# MainBoard_V03.net
KiCad netlist of a schematic drawn in Altium Designer
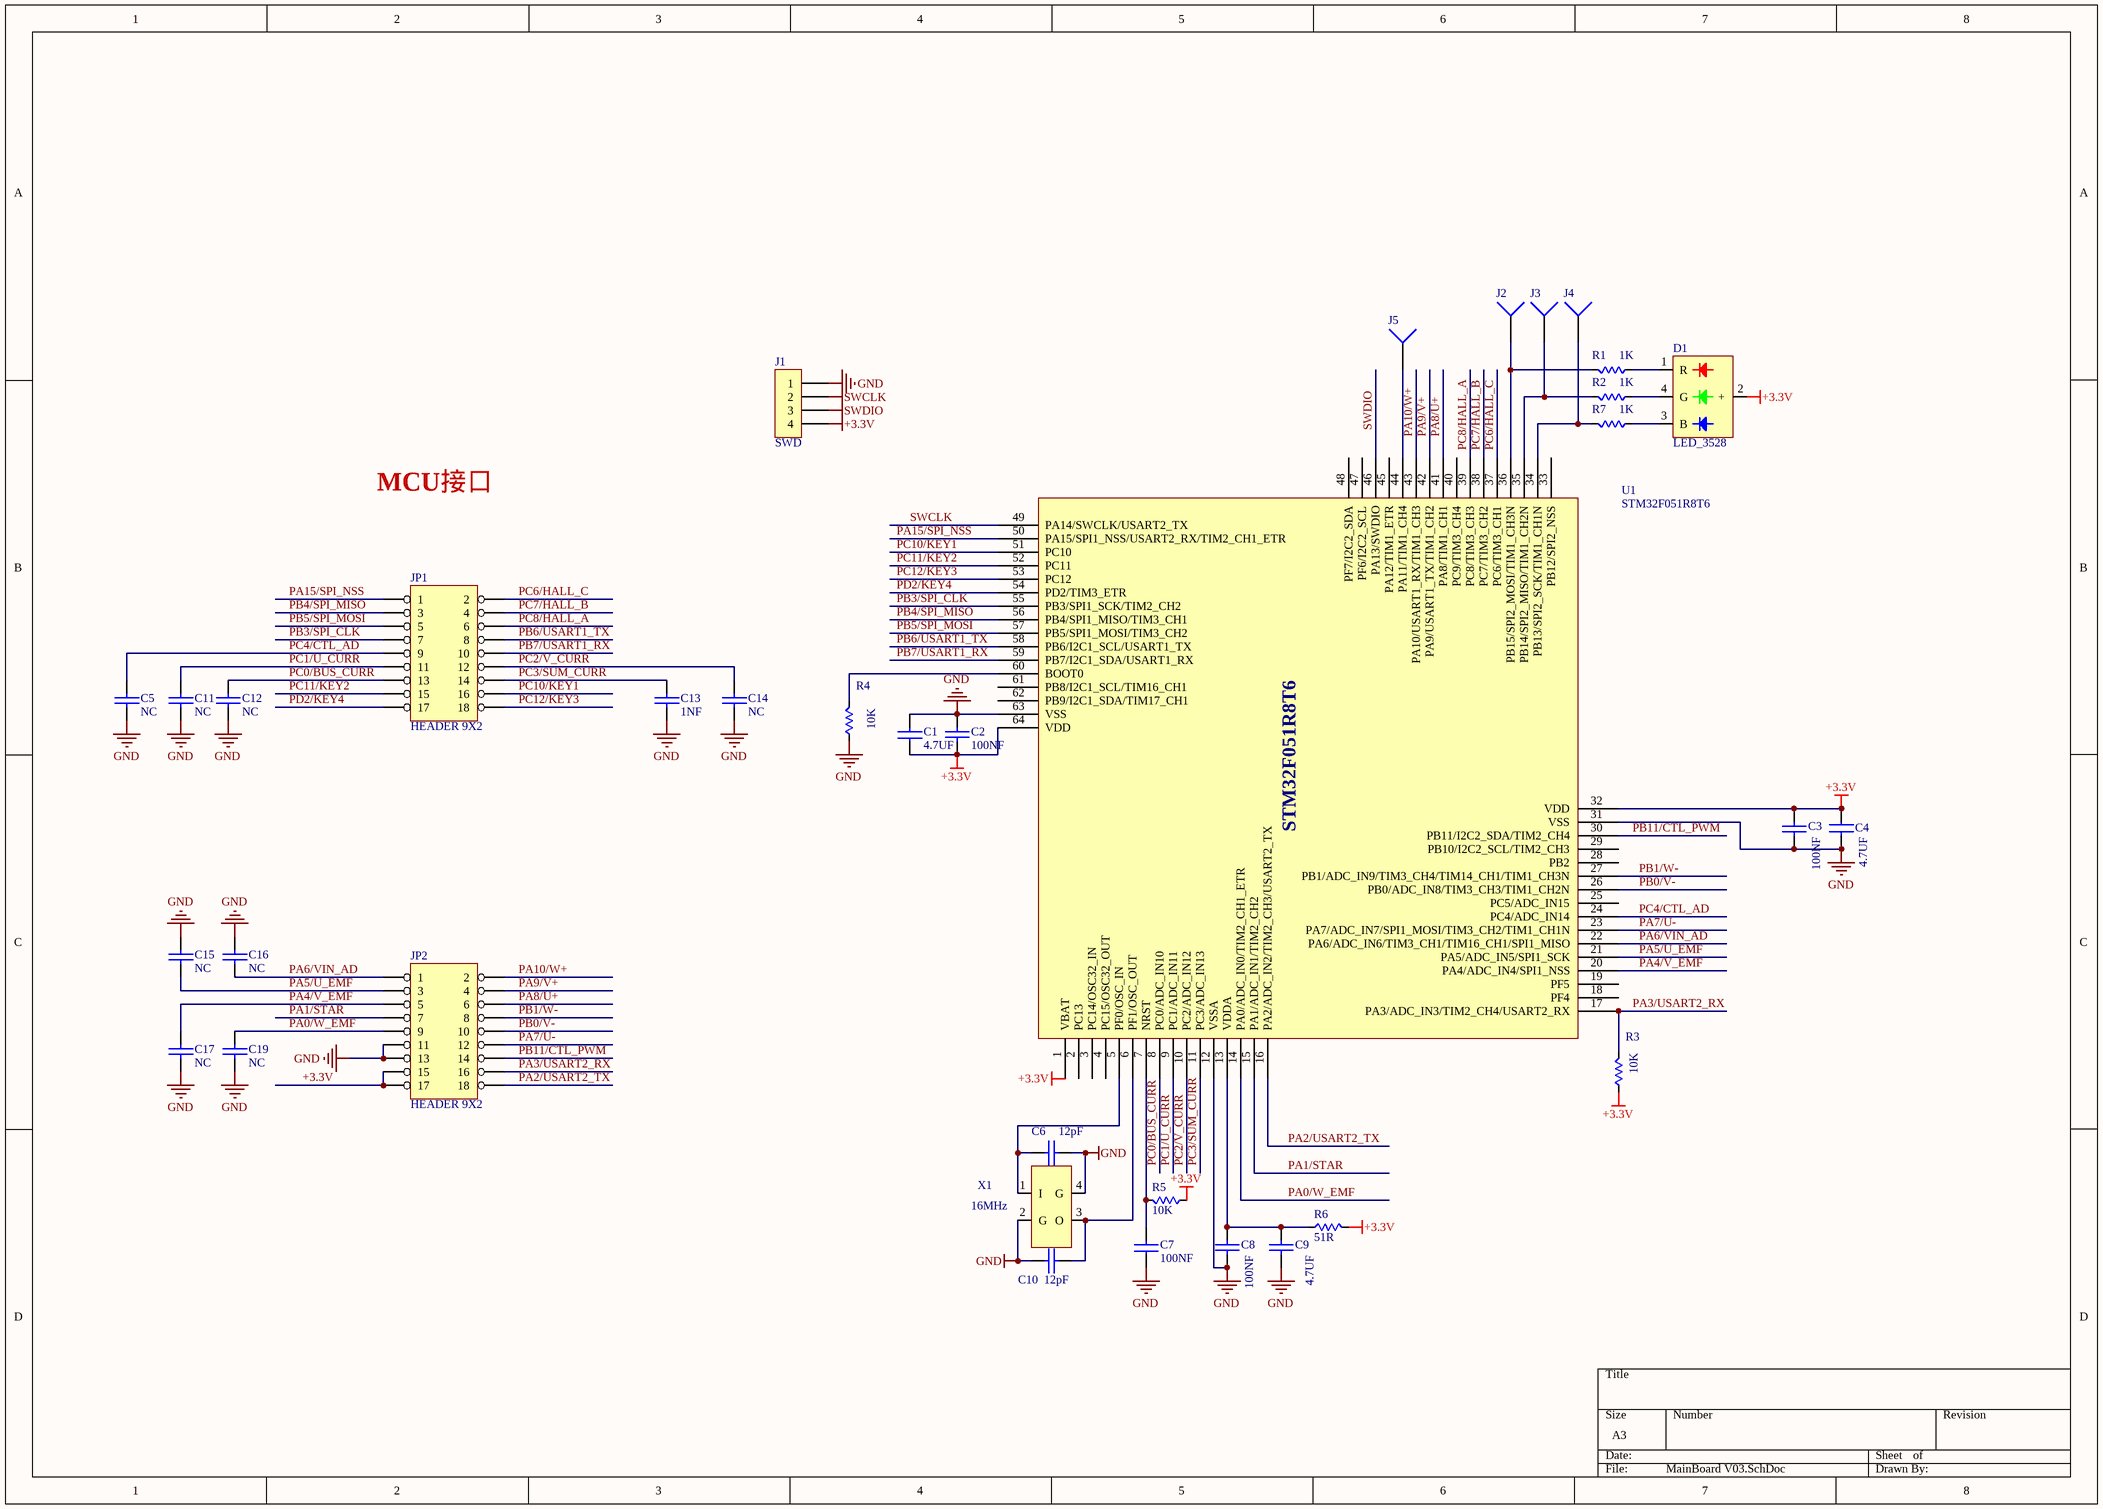
[diagram p0: MainBoard V03.SchDoc]

(export (version "E")
  (design (tool "Eeschema 10.0.6"))
  (components
    (comp (ref "C1") (value "4.7UF") (footprint "0805C") (libsource (lib "*") (part "CAP NP")))
    (comp (ref "C2")
      (value "100NF")
      (footprint "0603C")
      (description "Y02-02238")
      (libsource (lib "*") (part "CAP"))
    )
    (comp (ref "C3")
      (value "100NF")
      (footprint "0603C")
      (description "Y02-02238")
      (libsource (lib "*") (part "CAP"))
    )
    (comp (ref "C4") (value "4.7UF") (footprint "0805C") (libsource (lib "*") (part "CAP NP")))
    (comp (ref "C5")
      (value "NC")
      (footprint "0603C")
      (description "Y02-02238")
      (libsource (lib "*") (part "CAP"))
    )
    (comp (ref "C6")
      (value "12pF")
      (footprint "0603C")
      (description "Capacitor")
      (libsource (lib "*") (part "CAP"))
    )
    (comp (ref "C7")
      (value "100NF")
      (footprint "0603C")
      (description "Y02-02238")
      (libsource (lib "*") (part "CAP NP"))
    )
    (comp (ref "C8")
      (value "100NF")
      (footprint "0603C")
      (description "Y02-02238")
      (libsource (lib "*") (part "CAP"))
    )
    (comp (ref "C9")
      (value "4.7UF")
      (footprint "0805C")
      (description "Y02-02238")
      (libsource (lib "*") (part "CAP"))
    )
    (comp (ref "C10")
      (value "12pF")
      (footprint "0603C")
      (description "Capacitor")
      (libsource (lib "*") (part "CAP"))
    )
    (comp (ref "C11")
      (value "NC")
      (footprint "0603C")
      (description "Y02-02238")
      (libsource (lib "*") (part "CAP"))
    )
    (comp (ref "C12")
      (value "NC")
      (footprint "0603C")
      (description "Y02-02238")
      (libsource (lib "*") (part "CAP"))
    )
    (comp (ref "C13")
      (value "1NF")
      (footprint "0603C")
      (description "Y02-02238")
      (libsource (lib "*") (part "CAP"))
    )
    (comp (ref "C14")
      (value "NC")
      (footprint "0603C")
      (description "Y02-02238")
      (libsource (lib "*") (part "CAP"))
    )
    (comp (ref "C15")
      (value "NC")
      (footprint "0603C")
      (description "Y02-02238")
      (libsource (lib "*") (part "CAP"))
    )
    (comp (ref "C16")
      (value "NC")
      (footprint "0603C")
      (description "Y02-02238")
      (libsource (lib "*") (part "CAP"))
    )
    (comp (ref "C17")
      (value "NC")
      (footprint "0603C")
      (description "Y02-02238")
      (libsource (lib "*") (part "CAP"))
    )
    (comp (ref "C19")
      (value "NC")
      (footprint "0603C")
      (description "Y02-02238")
      (libsource (lib "*") (part "CAP"))
    )
    (comp (ref "D1") (value "LED_3528") (footprint "LED3528") (libsource (lib "COFLY-SCH") (part "LED_3528")))
    (comp (ref "J1")
      (value "SWD")
      (footprint "SIP4")
      (description "Connector")
      (libsource (lib "*") (part "CON4"))
    )
    (comp (ref "J2")
      (value "~")
      (footprint "TPJ1.3A")
      (description "Plug")
      (fields (field (name "PUBLISHER") "Altium Limited"))
      (libsource (lib "Miscellaneous Connectors") (part "Socket"))
    )
    (comp (ref "J3")
      (value "~")
      (footprint "TPJ1.3A")
      (description "Plug")
      (fields (field (name "PUBLISHER") "Altium Limited"))
      (libsource (lib "Miscellaneous Connectors") (part "Socket"))
    )
    (comp (ref "J4")
      (value "~")
      (footprint "TPJ1.3A")
      (description "Plug")
      (fields (field (name "PUBLISHER") "Altium Limited"))
      (libsource (lib "Miscellaneous Connectors") (part "Socket"))
    )
    (comp (ref "J5")
      (value "~")
      (footprint "PLUG")
      (description "Plug")
      (fields (field (name "PUBLISHER") "Altium Limited"))
      (libsource (lib "Miscellaneous Connectors") (part "Socket"))
    )
    (comp (ref "JP1")
      (value "HEADER 9X2")
      (footprint "SMT2.54-2X9-M-MIRROR")
      (libsource (lib "COFLY-SCH") (part "HEADER 9X2"))
    )
    (comp (ref "JP2")
      (value "HEADER 9X2")
      (footprint "SMT2.54-2X9-M-MIRROR")
      (libsource (lib "COFLY-SCH") (part "HEADER 9X2"))
    )
    (comp (ref "R1")
      (value "1K")
      (footprint "0603R")
      (description "Y02-00493")
      (libsource (lib "YUNEEC-SCH") (part "RES"))
    )
    (comp (ref "R2")
      (value "1K")
      (footprint "0603R")
      (description "Y02-00493")
      (libsource (lib "YUNEEC-SCH") (part "RES"))
    )
    (comp (ref "R3") (value "10K") (footprint "0603R") (libsource (lib "*") (part "RES")))
    (comp (ref "R4")
      (value "10K")
      (footprint "0603R")
      (description "Y02-01715")
      (libsource (lib "*") (part "RES"))
    )
    (comp (ref "R5")
      (value "10K")
      (footprint "0603R")
      (description "Y02-01715")
      (libsource (lib "*") (part "RES"))
    )
    (comp (ref "R6")
      (value "51R")
      (footprint "0603R")
      (description "Y02-01715")
      (libsource (lib "*") (part "RES"))
    )
    (comp (ref "R7")
      (value "1K")
      (footprint "0603R")
      (description "Y02-00493")
      (libsource (lib "YUNEEC-SCH") (part "RES"))
    )
    (comp (ref "U1")
      (value "STM32F051R8T6")
      (footprint "LQFP-64")
      (libsource (lib "COFLY-SCH") (part "STM32F051R8T6"))
    )
    (comp (ref "X1") (value "16MHz") (footprint "Y3225") (libsource (lib "*") (part "CON4A_1")))
  )
  (nets
    (net (code "1") (name "+3.3V") (class "Default")
      (node (ref "C1") (pin "1") (pinfunction "1_1") (pintype "passive"))
      (node (ref "C2") (pin "1") (pinfunction "1_1") (pintype "passive"))
      (node (ref "C3") (pin "1") (pinfunction "1_1") (pintype "passive"))
      (node (ref "C4") (pin "1") (pinfunction "1_1") (pintype "passive"))
      (node (ref "D1") (pin "2") (pinfunction "+_2") (pintype "passive"))
      (node (ref "J1") (pin "4") (pinfunction "4_4") (pintype "passive"))
      (node (ref "JP2") (pin "15") (pinfunction "15_15") (pintype "passive"))
      (node (ref "JP2") (pin "17") (pinfunction "17_17") (pintype "passive"))
      (node (ref "R3") (pin "2") (pinfunction "2_2") (pintype "passive"))
      (node (ref "R5") (pin "2") (pinfunction "2_2") (pintype "passive"))
      (node (ref "R6") (pin "1") (pinfunction "1_1") (pintype "passive"))
      (node (ref "U1") (pin "1") (pinfunction "VBAT_1") (pintype "passive"))
      (node (ref "U1") (pin "32") (pinfunction "VDD_32") (pintype "passive"))
      (node (ref "U1") (pin "64") (pinfunction "VDD_64") (pintype "passive"))
    )
    (net (code "2") (name "/PA0{slash}W_EMF") (class "Default")
      (node (ref "C19") (pin "1") (pinfunction "1_1") (pintype "passive"))
      (node (ref "JP2") (pin "9") (pinfunction "9_9") (pintype "passive"))
      (node (ref "U1") (pin "14") (pinfunction "PA0/ADC_IN0/TIM2_CH1_ETR_14") (pintype "passive"))
    )
    (net (code "3") (name "/PA1{slash}STAR") (class "Default")
      (node (ref "JP2") (pin "7") (pinfunction "7_7") (pintype "passive"))
      (node (ref "U1") (pin "15") (pinfunction "PA1/ADC_IN1/TIM2_CH2_15") (pintype "passive"))
    )
    (net (code "4") (name "/PA2{slash}USART2_TX") (class "Default")
      (node (ref "JP2") (pin "18") (pinfunction "18_18") (pintype "passive"))
      (node (ref "U1") (pin "16") (pinfunction "PA2/ADC_IN2/TIM2_CH3/USART2_TX_16") (pintype "passive"))
    )
    (net (code "5") (name "/PA3{slash}USART2_RX") (class "Default")
      (node (ref "JP2") (pin "16") (pinfunction "16_16") (pintype "passive"))
      (node (ref "R3") (pin "1") (pinfunction "1_1") (pintype "passive"))
      (node (ref "U1") (pin "17") (pinfunction "PA3/ADC_IN3/TIM2_CH4/USART2_RX_17") (pintype "passive"))
    )
    (net (code "6") (name "/PA4{slash}V_EMF") (class "Default")
      (node (ref "C17") (pin "1") (pinfunction "1_1") (pintype "passive"))
      (node (ref "JP2") (pin "5") (pinfunction "5_5") (pintype "passive"))
      (node (ref "U1") (pin "20") (pinfunction "PA4/ADC_IN4/SPI1_NSS_20") (pintype "passive"))
    )
    (net (code "7") (name "/PA5{slash}U_EMF") (class "Default")
      (node (ref "C15") (pin "1") (pinfunction "1_1") (pintype "passive"))
      (node (ref "JP2") (pin "3") (pinfunction "3_3") (pintype "passive"))
      (node (ref "U1") (pin "21") (pinfunction "PA5/ADC_IN5/SPI1_SCK_21") (pintype "passive"))
    )
    (net (code "8") (name "/PA6{slash}VIN_AD") (class "Default")
      (node (ref "C16") (pin "1") (pinfunction "1_1") (pintype "passive"))
      (node (ref "JP2") (pin "1") (pinfunction "1_1") (pintype "passive"))
      (node (ref "U1") (pin "22") (pinfunction "PA6/ADC_IN6/TIM3_CH1/TIM16_CH1/SPI1_MISO_22") (pintype "passive"))
    )
    (net (code "9") (name "/PA7{slash}U-") (class "Default")
      (node (ref "JP2") (pin "12") (pinfunction "12_12") (pintype "passive"))
      (node (ref "U1") (pin "23") (pinfunction "PA7/ADC_IN7/SPI1_MOSI/TIM3_CH2/TIM1_CH1N_23") (pintype "passive"))
    )
    (net (code "10") (name "/PA8{slash}U+") (class "Default")
      (node (ref "JP2") (pin "6") (pinfunction "6_6") (pintype "passive"))
      (node (ref "U1") (pin "41") (pinfunction "PA8/TIM1_CH1_41") (pintype "passive"))
    )
    (net (code "11") (name "/PA9{slash}V+") (class "Default")
      (node (ref "JP2") (pin "4") (pinfunction "4_4") (pintype "passive"))
      (node (ref "U1") (pin "42") (pinfunction "PA9/USART1_TX/TIM1_CH2_42") (pintype "passive"))
    )
    (net (code "12") (name "/PA10{slash}W+") (class "Default")
      (node (ref "JP2") (pin "2") (pinfunction "2_2") (pintype "passive"))
      (node (ref "U1") (pin "43") (pinfunction "PA10/USART1_RX/TIM1_CH3_43") (pintype "passive"))
    )
    (net (code "13") (name "/PA15{slash}SPI_NSS") (class "Default")
      (node (ref "JP1") (pin "1") (pinfunction "1_1") (pintype "passive"))
      (node (ref "U1") (pin "50") (pinfunction "PA15/SPI1_NSS/USART2_RX/TIM2_CH1_ETR_50") (pintype "passive"))
    )
    (net (code "14") (name "/PB0{slash}V-") (class "Default")
      (node (ref "JP2") (pin "10") (pinfunction "10_10") (pintype "passive"))
      (node (ref "U1") (pin "26") (pinfunction "PB0/ADC_IN8/TIM3_CH3/TIM1_CH2N_26") (pintype "passive"))
    )
    (net (code "15") (name "/PB1{slash}W-") (class "Default")
      (node (ref "JP2") (pin "8") (pinfunction "8_8") (pintype "passive"))
      (node (ref "U1") (pin "27") (pinfunction "PB1/ADC_IN9/TIM3_CH4/TIM14_CH1/TIM1_CH3N_27") (pintype "passive"))
    )
    (net (code "16") (name "/PB3{slash}SPI_CLK") (class "Default")
      (node (ref "JP1") (pin "7") (pinfunction "7_7") (pintype "passive"))
      (node (ref "U1") (pin "55") (pinfunction "PB3/SPI1_SCK/TIM2_CH2_55") (pintype "passive"))
    )
    (net (code "17") (name "/PB4{slash}SPI_MISO") (class "Default")
      (node (ref "JP1") (pin "3") (pinfunction "3_3") (pintype "passive"))
      (node (ref "U1") (pin "56") (pinfunction "PB4/SPI1_MISO/TIM3_CH1_56") (pintype "passive"))
    )
    (net (code "18") (name "/PB5{slash}SPI_MOSI") (class "Default")
      (node (ref "JP1") (pin "5") (pinfunction "5_5") (pintype "passive"))
      (node (ref "U1") (pin "57") (pinfunction "PB5/SPI1_MOSI/TIM3_CH2_57") (pintype "passive"))
    )
    (net (code "19") (name "/PB6{slash}USART1_TX") (class "Default")
      (node (ref "JP1") (pin "8") (pinfunction "8_8") (pintype "passive"))
      (node (ref "U1") (pin "58") (pinfunction "PB6/I2C1_SCL/USART1_TX_58") (pintype "passive"))
    )
    (net (code "20") (name "/PB7{slash}USART1_RX") (class "Default")
      (node (ref "JP1") (pin "10") (pinfunction "10_10") (pintype "passive"))
      (node (ref "U1") (pin "59") (pinfunction "PB7/I2C1_SDA/USART1_RX_59") (pintype "passive"))
    )
    (net (code "21") (name "/PB11{slash}CTL_PWM") (class "Default")
      (node (ref "JP2") (pin "14") (pinfunction "14_14") (pintype "passive"))
      (node (ref "U1") (pin "30") (pinfunction "PB11/I2C2_SDA/TIM2_CH4_30") (pintype "passive"))
    )
    (net (code "22") (name "/PC0{slash}BUS_CURR") (class "Default")
      (node (ref "C12") (pin "1") (pinfunction "1_1") (pintype "passive"))
      (node (ref "JP1") (pin "13") (pinfunction "13_13") (pintype "passive"))
      (node (ref "U1") (pin "8") (pinfunction "PC0/ADC_IN10_8") (pintype "passive"))
    )
    (net (code "23") (name "/PC1{slash}U_CURR") (class "Default")
      (node (ref "C11") (pin "1") (pinfunction "1_1") (pintype "passive"))
      (node (ref "JP1") (pin "11") (pinfunction "11_11") (pintype "passive"))
      (node (ref "U1") (pin "9") (pinfunction "PC1/ADC_IN11_9") (pintype "passive"))
    )
    (net (code "24") (name "/PC2{slash}V_CURR") (class "Default")
      (node (ref "C14") (pin "1") (pinfunction "1_1") (pintype "passive"))
      (node (ref "JP1") (pin "12") (pinfunction "12_12") (pintype "passive"))
      (node (ref "U1") (pin "10") (pinfunction "PC2/ADC_IN12_10") (pintype "passive"))
    )
    (net (code "25") (name "/PC3{slash}SUM_CURR") (class "Default")
      (node (ref "C13") (pin "1") (pinfunction "1_1") (pintype "passive"))
      (node (ref "JP1") (pin "14") (pinfunction "14_14") (pintype "passive"))
      (node (ref "U1") (pin "11") (pinfunction "PC3/ADC_IN13_11") (pintype "passive"))
    )
    (net (code "26") (name "/PC4{slash}CTL_AD") (class "Default")
      (node (ref "C5") (pin "1") (pinfunction "1_1") (pintype "passive"))
      (node (ref "JP1") (pin "9") (pinfunction "9_9") (pintype "passive"))
      (node (ref "U1") (pin "24") (pinfunction "PC4/ADC_IN14_24") (pintype "passive"))
    )
    (net (code "27") (name "/PC6{slash}HALL_C") (class "Default")
      (node (ref "JP1") (pin "2") (pinfunction "2_2") (pintype "passive"))
      (node (ref "U1") (pin "37") (pinfunction "PC6/TIM3_CH1_37") (pintype "passive"))
    )
    (net (code "28") (name "/PC7{slash}HALL_B") (class "Default")
      (node (ref "JP1") (pin "4") (pinfunction "4_4") (pintype "passive"))
      (node (ref "U1") (pin "38") (pinfunction "PC7/TIM3_CH2_38") (pintype "passive"))
    )
    (net (code "29") (name "/PC8{slash}HALL_A") (class "Default")
      (node (ref "JP1") (pin "6") (pinfunction "6_6") (pintype "passive"))
      (node (ref "U1") (pin "39") (pinfunction "PC8/TIM3_CH3_39") (pintype "passive"))
    )
    (net (code "30") (name "/PC10{slash}KEY1") (class "Default")
      (node (ref "JP1") (pin "16") (pinfunction "16_16") (pintype "passive"))
      (node (ref "U1") (pin "51") (pinfunction "PC10_51") (pintype "passive"))
    )
    (net (code "31") (name "/PC11{slash}KEY2") (class "Default")
      (node (ref "JP1") (pin "15") (pinfunction "15_15") (pintype "passive"))
      (node (ref "U1") (pin "52") (pinfunction "PC11_52") (pintype "passive"))
    )
    (net (code "32") (name "/PC12{slash}KEY3") (class "Default")
      (node (ref "JP1") (pin "18") (pinfunction "18_18") (pintype "passive"))
      (node (ref "U1") (pin "53") (pinfunction "PC12_53") (pintype "passive"))
    )
    (net (code "33") (name "/PD2{slash}KEY4") (class "Default")
      (node (ref "JP1") (pin "17") (pinfunction "17_17") (pintype "passive"))
      (node (ref "U1") (pin "54") (pinfunction "PD2/TIM3_ETR_54") (pintype "passive"))
    )
    (net (code "34") (name "GND") (class "Default")
      (node (ref "C1") (pin "2") (pinfunction "2_2") (pintype "passive"))
      (node (ref "C10") (pin "1") (pinfunction "1_1") (pintype "passive"))
      (node (ref "C11") (pin "2") (pinfunction "2_2") (pintype "passive"))
      (node (ref "C12") (pin "2") (pinfunction "2_2") (pintype "passive"))
      (node (ref "C13") (pin "2") (pinfunction "2_2") (pintype "passive"))
      (node (ref "C14") (pin "2") (pinfunction "2_2") (pintype "passive"))
      (node (ref "C15") (pin "2") (pinfunction "2_2") (pintype "passive"))
      (node (ref "C16") (pin "2") (pinfunction "2_2") (pintype "passive"))
      (node (ref "C17") (pin "2") (pinfunction "2_2") (pintype "passive"))
      (node (ref "C19") (pin "2") (pinfunction "2_2") (pintype "passive"))
      (node (ref "C2") (pin "2") (pinfunction "2_2") (pintype "passive"))
      (node (ref "C3") (pin "2") (pinfunction "2_2") (pintype "passive"))
      (node (ref "C4") (pin "2") (pinfunction "2_2") (pintype "passive"))
      (node (ref "C5") (pin "2") (pinfunction "2_2") (pintype "passive"))
      (node (ref "C6") (pin "1") (pinfunction "1_1") (pintype "passive"))
      (node (ref "C7") (pin "1") (pinfunction "1_1") (pintype "passive"))
      (node (ref "C8") (pin "2") (pinfunction "2_2") (pintype "passive"))
      (node (ref "C9") (pin "2") (pinfunction "2_2") (pintype "passive"))
      (node (ref "J1") (pin "1") (pinfunction "1_1") (pintype "passive"))
      (node (ref "JP2") (pin "11") (pinfunction "11_11") (pintype "passive"))
      (node (ref "JP2") (pin "13") (pinfunction "13_13") (pintype "passive"))
      (node (ref "R4") (pin "2") (pinfunction "2_2") (pintype "passive"))
      (node (ref "U1") (pin "12") (pinfunction "VSSA_12") (pintype "passive"))
      (node (ref "U1") (pin "31") (pinfunction "VSS_31") (pintype "passive"))
      (node (ref "U1") (pin "63") (pinfunction "VSS_63") (pintype "passive"))
      (node (ref "X1") (pin "2") (pinfunction "G_2") (pintype "passive"))
      (node (ref "X1") (pin "4") (pinfunction "G_4") (pintype "passive"))
    )
    (net (code "35") (name "Net-(D1-B)") (class "Default")
      (node (ref "D1") (pin "3") (pinfunction "B_3") (pintype "passive"))
      (node (ref "R7") (pin "1") (pinfunction "1_1") (pintype "passive"))
    )
    (net (code "36") (name "Net-(D1-G)") (class "Default")
      (node (ref "D1") (pin "4") (pinfunction "G_4") (pintype "passive"))
      (node (ref "R2") (pin "1") (pinfunction "1_1") (pintype "passive"))
    )
    (net (code "37") (name "Net-(D1-R)") (class "Default")
      (node (ref "D1") (pin "1") (pinfunction "R_1") (pintype "passive"))
      (node (ref "R1") (pin "1") (pinfunction "1_1") (pintype "passive"))
    )
    (net (code "38") (name "Net-(U1-BOOT0)") (class "Default")
      (node (ref "R4") (pin "1") (pinfunction "1_1") (pintype "passive"))
      (node (ref "U1") (pin "60") (pinfunction "BOOT0_60") (pintype "passive"))
    )
    (net (code "39") (name "Net-(U1-NRST)") (class "Default")
      (node (ref "C7") (pin "2") (pinfunction "2_2") (pintype "passive"))
      (node (ref "R5") (pin "1") (pinfunction "1_1") (pintype "passive"))
      (node (ref "U1") (pin "7") (pinfunction "NRST_7") (pintype "passive"))
    )
    (net (code "40") (name "Net-(U1-PA11{slash}TIM1_CH4)") (class "Default")
      (node (ref "J5") (pin "1") (pinfunction "1_1") (pintype "passive"))
      (node (ref "U1") (pin "44") (pinfunction "PA11/TIM1_CH4_44") (pintype "passive"))
    )
    (net (code "41") (name "Net-(U1-PB13{slash}SPI2_SCK{slash}TIM1_CH1N)") (class "Default")
      (node (ref "J4") (pin "1") (pinfunction "1_1") (pintype "passive"))
      (node (ref "R7") (pin "2") (pinfunction "2_2") (pintype "passive"))
      (node (ref "U1") (pin "34") (pinfunction "PB13/SPI2_SCK/TIM1_CH1N_34") (pintype "passive"))
    )
    (net (code "42") (name "Net-(U1-PB14{slash}SPI2_MISO{slash}TIM1_CH2N)") (class "Default")
      (node (ref "J3") (pin "1") (pinfunction "1_1") (pintype "passive"))
      (node (ref "R2") (pin "2") (pinfunction "2_2") (pintype "passive"))
      (node (ref "U1") (pin "35") (pinfunction "PB14/SPI2_MISO/TIM1_CH2N_35") (pintype "passive"))
    )
    (net (code "43") (name "Net-(U1-PB15{slash}SPI2_MOSI{slash}TIM1_CH3N)") (class "Default")
      (node (ref "J2") (pin "1") (pinfunction "1_1") (pintype "passive"))
      (node (ref "R1") (pin "2") (pinfunction "2_2") (pintype "passive"))
      (node (ref "U1") (pin "36") (pinfunction "PB15/SPI2_MOSI/TIM1_CH3N_36") (pintype "passive"))
    )
    (net (code "44") (name "Net-(U1-PF0{slash}OSC_IN)") (class "Default")
      (node (ref "C6") (pin "2") (pinfunction "2_2") (pintype "passive"))
      (node (ref "U1") (pin "5") (pinfunction "PF0/OSC_IN_5") (pintype "passive"))
      (node (ref "X1") (pin "1") (pinfunction "I_1") (pintype "passive"))
    )
    (net (code "45") (name "Net-(U1-PF1{slash}OSC_OUT)") (class "Default")
      (node (ref "C10") (pin "2") (pinfunction "2_2") (pintype "passive"))
      (node (ref "U1") (pin "6") (pinfunction "PF1/OSC_OUT_6") (pintype "passive"))
      (node (ref "X1") (pin "3") (pinfunction "O_3") (pintype "passive"))
    )
    (net (code "46") (name "Net-(U1-VDDA)") (class "Default")
      (node (ref "C8") (pin "1") (pinfunction "1_1") (pintype "passive"))
      (node (ref "C9") (pin "1") (pinfunction "1_1") (pintype "passive"))
      (node (ref "R6") (pin "2") (pinfunction "2_2") (pintype "passive"))
      (node (ref "U1") (pin "13") (pinfunction "VDDA_13") (pintype "passive"))
    )
    (net (code "47") (name "SWCLK") (class "Default")
      (node (ref "J1") (pin "2") (pinfunction "2_2") (pintype "passive"))
      (node (ref "U1") (pin "49") (pinfunction "PA14/SWCLK/USART2_TX_49") (pintype "passive"))
    )
    (net (code "48") (name "SWDIO") (class "Default")
      (node (ref "J1") (pin "3") (pinfunction "3_3") (pintype "passive"))
      (node (ref "U1") (pin "46") (pinfunction "PA13/SWDIO_46") (pintype "passive"))
    )
    (net (code "49") (name "unconnected-(U1-PA12{slash}TIM1_ETR-Pad45)") (class "Default")
      (node (ref "U1") (pin "45") (pinfunction "PA12/TIM1_ETR_45") (pintype "passive"))
    )
    (net (code "50") (name "unconnected-(U1-PB2-Pad28)") (class "Default")
      (node (ref "U1") (pin "28") (pinfunction "PB2_28") (pintype "passive"))
    )
    (net (code "51") (name "unconnected-(U1-PB8{slash}I2C1_SCL{slash}TIM16_CH1-Pad61)") (class "Default")
      (node (ref "U1") (pin "61") (pinfunction "PB8/I2C1_SCL/TIM16_CH1_61") (pintype "passive"))
    )
    (net (code "52") (name "unconnected-(U1-PB9{slash}I2C1_SDA{slash}TIM17_CH1-Pad62)") (class "Default")
      (node (ref "U1") (pin "62") (pinfunction "PB9/I2C1_SDA/TIM17_CH1_62") (pintype "passive"))
    )
    (net (code "53") (name "unconnected-(U1-PB10{slash}I2C2_SCL{slash}TIM2_CH3-Pad29)") (class "Default")
      (node (ref "U1") (pin "29") (pinfunction "PB10/I2C2_SCL/TIM2_CH3_29") (pintype "passive"))
    )
    (net (code "54") (name "unconnected-(U1-PB12{slash}SPI2_NSS-Pad33)") (class "Default")
      (node (ref "U1") (pin "33") (pinfunction "PB12/SPI2_NSS_33") (pintype "passive"))
    )
    (net (code "55") (name "unconnected-(U1-PC5{slash}ADC_IN15-Pad25)") (class "Default")
      (node (ref "U1") (pin "25") (pinfunction "PC5/ADC_IN15_25") (pintype "passive"))
    )
    (net (code "56") (name "unconnected-(U1-PC9{slash}TIM3_CH4-Pad40)") (class "Default")
      (node (ref "U1") (pin "40") (pinfunction "PC9/TIM3_CH4_40") (pintype "passive"))
    )
    (net (code "57") (name "unconnected-(U1-PC13-Pad2)") (class "Default")
      (node (ref "U1") (pin "2") (pinfunction "PC13_2") (pintype "passive"))
    )
    (net (code "58") (name "unconnected-(U1-PC14{slash}OSC32_IN-Pad3)") (class "Default")
      (node (ref "U1") (pin "3") (pinfunction "PC14/OSC32_IN_3") (pintype "passive"))
    )
    (net (code "59") (name "unconnected-(U1-PC15{slash}OSC32_OUT-Pad4)") (class "Default")
      (node (ref "U1") (pin "4") (pinfunction "PC15/OSC32_OUT_4") (pintype "passive"))
    )
    (net (code "60") (name "unconnected-(U1-PF4-Pad18)") (class "Default")
      (node (ref "U1") (pin "18") (pinfunction "PF4_18") (pintype "passive"))
    )
    (net (code "61") (name "unconnected-(U1-PF5-Pad19)") (class "Default")
      (node (ref "U1") (pin "19") (pinfunction "PF5_19") (pintype "passive"))
    )
    (net (code "62") (name "unconnected-(U1-PF6{slash}I2C2_SCL-Pad47)") (class "Default")
      (node (ref "U1") (pin "47") (pinfunction "PF6/I2C2_SCL_47") (pintype "passive"))
    )
    (net (code "63") (name "unconnected-(U1-PF7{slash}I2C2_SDA-Pad48)") (class "Default")
      (node (ref "U1") (pin "48") (pinfunction "PF7/I2C2_SDA_48") (pintype "passive"))
    )
  )
)
